# safebox_professional.net
KiCad netlist of a schematic drawn in EAGLE
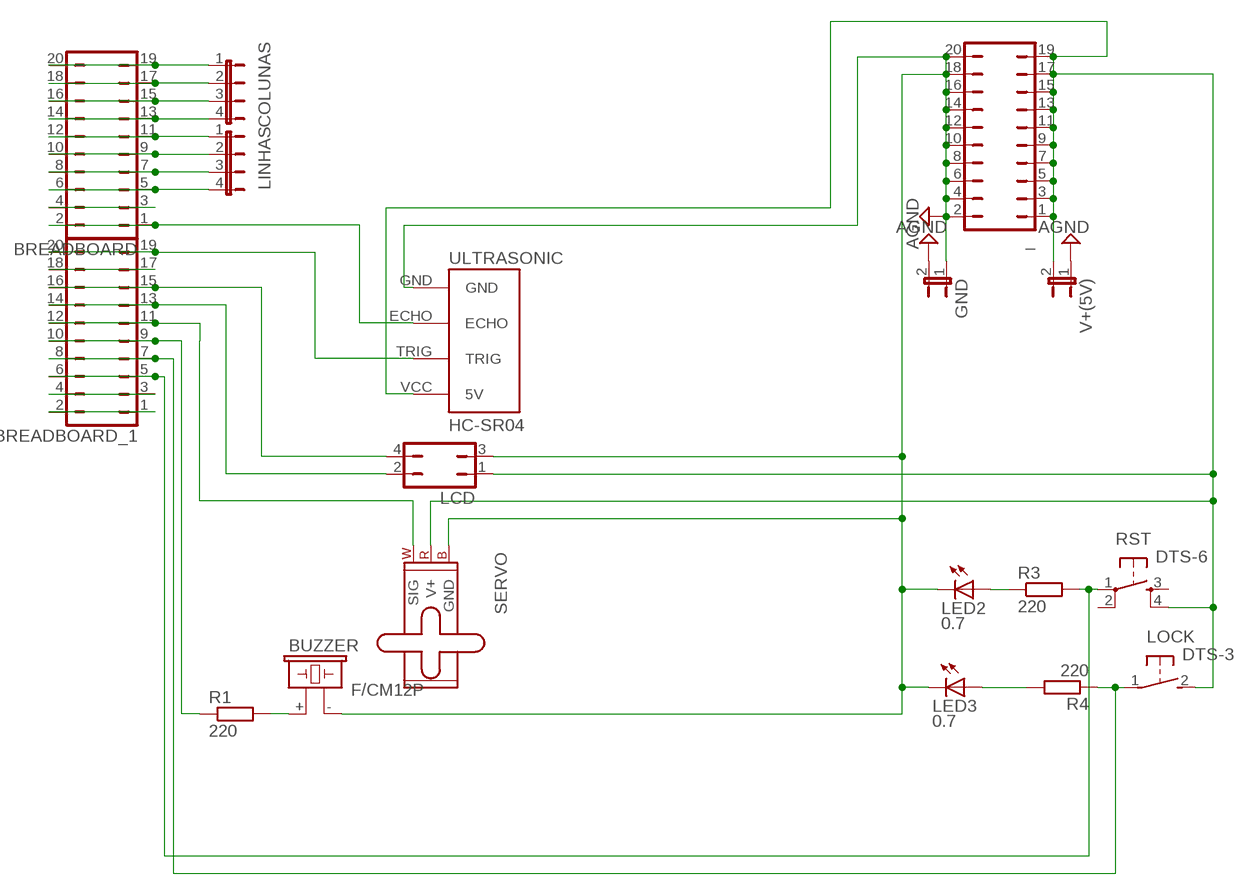
[diagram p0: schematic, sheet 1]

(export (version "E")
  (design (tool "Eeschema 10.0.6"))
  (components
    (comp (ref "BREADBOARD")
      (value "JP10Q")
      (footprint "eagle-import:JP10Q")
      (libsource (lib "eagle-import") (part "JP10Q"))
    )
    (comp (ref "BREADBOARD_1")
      (value "JP10Q")
      (footprint "eagle-import:JP10Q")
      (libsource (lib "eagle-import") (part "JP10Q"))
    )
    (comp (ref "BUZZER")
      (value "F/CM12P")
      (footprint "eagle-import:F_CM12P")
      (libsource (lib "eagle-import") (part "F/CM12P"))
    )
    (comp (ref "COLUNAS")
      (value "JP4E")
      (footprint "eagle-import:JP4")
      (libsource (lib "eagle-import") (part "JP4E"))
    )
    (comp (ref "GND")
      (value "JP1E")
      (footprint "eagle-import:JP1")
      (libsource (lib "eagle-import") (part "JP1E"))
    )
    (comp (ref "LCD")
      (value "JP2Q")
      (footprint "eagle-import:JP2Q")
      (libsource (lib "eagle-import") (part "JP2Q"))
    )
    (comp (ref "LED2")
      (value "0.7")
      (footprint "eagle-import:LED5MM")
      (libsource (lib "eagle-import") (part "LED5MM"))
    )
    (comp (ref "LED3")
      (value "0.7")
      (footprint "eagle-import:LED5MM")
      (libsource (lib "eagle-import") (part "LED5MM"))
    )
    (comp (ref "LINHAS")
      (value "JP4E")
      (footprint "eagle-import:JP4")
      (libsource (lib "eagle-import") (part "JP4E"))
    )
    (comp (ref "LOCK")
      (value "DTS-3")
      (footprint "eagle-import:DTS-3")
      (libsource (lib "eagle-import") (part "DTS-3"))
    )
    (comp (ref "M2")
      (value "SERVO")
      (footprint "eagle-import:1X03")
      (libsource (lib "eagle-import") (part "SERVO"))
    )
    (comp (ref "R1")
      (value "220")
      (footprint "eagle-import:0207_12")
      (libsource (lib "eagle-import") (part "R-EU_0207/12"))
    )
    (comp (ref "R3")
      (value "220")
      (footprint "eagle-import:0207_12")
      (libsource (lib "eagle-import") (part "R-EU_0207/12"))
    )
    (comp (ref "R4")
      (value "220")
      (footprint "eagle-import:0207_12")
      (libsource (lib "eagle-import") (part "R-EU_0207/12"))
    )
    (comp (ref "RST")
      (value "DTS-6")
      (footprint "eagle-import:DTS-6")
      (libsource (lib "eagle-import") (part "DTS-6"))
    )
    (comp (ref "ULTRASONIC")
      (value "HC-SR04")
      (footprint "eagle-import:HC-SR04_FOOTPRINT")
      (libsource (lib "eagle-import") (part "HC-SR04"))
    )
    (comp (ref "V+(5V)")
      (value "JP1E")
      (footprint "eagle-import:JP1")
      (libsource (lib "eagle-import") (part "JP1E"))
    )
    (comp (ref "_")
      (value "JP10Q")
      (footprint "eagle-import:JP10Q")
      (libsource (lib "eagle-import") (part "JP10Q"))
    )
  )
  (nets
    (net (code "1") (name "AGND") (class "Default")
      (node (ref "BUZZER") (pin "-") (pinfunction "2_-") (pintype "passive"))
      (node (ref "GND") (pin "1") (pinfunction "1_1") (pintype "passive"))
      (node (ref "GND") (pin "2") (pinfunction "2_2") (pintype "passive"))
      (node (ref "LCD") (pin "3") (pinfunction "3_3") (pintype "passive"))
      (node (ref "LED2") (pin "K") (pinfunction "C_K") (pintype "passive"))
      (node (ref "LED3") (pin "K") (pinfunction "C_K") (pintype "passive"))
      (node (ref "M2") (pin "3") (pinfunction "GND_3") (pintype "bidirectional"))
      (node (ref "ULTRASONIC") (pin "GND") (pinfunction "GND_GND") (pintype "bidirectional"))
      (node (ref "V+(5V)") (pin "1") (pinfunction "1_1") (pintype "passive"))
      (node (ref "_") (pin "10") (pinfunction "10_10") (pintype "passive"))
      (node (ref "_") (pin "12") (pinfunction "12_12") (pintype "passive"))
      (node (ref "_") (pin "14") (pinfunction "14_14") (pintype "passive"))
      (node (ref "_") (pin "16") (pinfunction "16_16") (pintype "passive"))
      (node (ref "_") (pin "18") (pinfunction "18_18") (pintype "passive"))
      (node (ref "_") (pin "2") (pinfunction "2_2") (pintype "passive"))
      (node (ref "_") (pin "20") (pinfunction "20_20") (pintype "passive"))
      (node (ref "_") (pin "4") (pinfunction "4_4") (pintype "passive"))
      (node (ref "_") (pin "6") (pinfunction "6_6") (pintype "passive"))
      (node (ref "_") (pin "8") (pinfunction "8_8") (pintype "passive"))
    )
    (net (code "2") (name "Net-(BREADBOARD-Pad1)") (class "Default")
      (node (ref "BREADBOARD") (pin "1") (pinfunction "1_1") (pintype "passive"))
      (node (ref "BREADBOARD") (pin "2") (pinfunction "2_2") (pintype "passive"))
      (node (ref "ULTRASONIC") (pin "ECHO") (pinfunction "ECHO_ECHO") (pintype "bidirectional"))
    )
    (net (code "3") (name "Net-(BREADBOARD-Pad3)") (class "Default")
      (node (ref "BREADBOARD") (pin "3") (pinfunction "3_3") (pintype "passive"))
      (node (ref "BREADBOARD") (pin "4") (pinfunction "4_4") (pintype "passive"))
    )
    (net (code "4") (name "Net-(BREADBOARD-Pad5)") (class "Default")
      (node (ref "BREADBOARD") (pin "5") (pinfunction "5_5") (pintype "passive"))
      (node (ref "BREADBOARD") (pin "6") (pinfunction "6_6") (pintype "passive"))
      (node (ref "LINHAS") (pin "4") (pinfunction "4_4") (pintype "passive"))
    )
    (net (code "5") (name "Net-(BREADBOARD-Pad7)") (class "Default")
      (node (ref "BREADBOARD") (pin "7") (pinfunction "7_7") (pintype "passive"))
      (node (ref "BREADBOARD") (pin "8") (pinfunction "8_8") (pintype "passive"))
      (node (ref "LINHAS") (pin "3") (pinfunction "3_3") (pintype "passive"))
    )
    (net (code "6") (name "Net-(BREADBOARD-Pad10)") (class "Default")
      (node (ref "BREADBOARD") (pin "10") (pinfunction "10_10") (pintype "passive"))
      (node (ref "BREADBOARD") (pin "9") (pinfunction "9_9") (pintype "passive"))
      (node (ref "LINHAS") (pin "2") (pinfunction "2_2") (pintype "passive"))
    )
    (net (code "7") (name "Net-(BREADBOARD-Pad11)") (class "Default")
      (node (ref "BREADBOARD") (pin "11") (pinfunction "11_11") (pintype "passive"))
      (node (ref "BREADBOARD") (pin "12") (pinfunction "12_12") (pintype "passive"))
      (node (ref "LINHAS") (pin "1") (pinfunction "1_1") (pintype "passive"))
    )
    (net (code "8") (name "Net-(BREADBOARD-Pad13)") (class "Default")
      (node (ref "BREADBOARD") (pin "13") (pinfunction "13_13") (pintype "passive"))
      (node (ref "BREADBOARD") (pin "14") (pinfunction "14_14") (pintype "passive"))
      (node (ref "COLUNAS") (pin "4") (pinfunction "4_4") (pintype "passive"))
    )
    (net (code "9") (name "Net-(BREADBOARD-Pad15)") (class "Default")
      (node (ref "BREADBOARD") (pin "15") (pinfunction "15_15") (pintype "passive"))
      (node (ref "BREADBOARD") (pin "16") (pinfunction "16_16") (pintype "passive"))
      (node (ref "COLUNAS") (pin "3") (pinfunction "3_3") (pintype "passive"))
    )
    (net (code "10") (name "Net-(BREADBOARD-Pad17)") (class "Default")
      (node (ref "BREADBOARD") (pin "17") (pinfunction "17_17") (pintype "passive"))
      (node (ref "BREADBOARD") (pin "18") (pinfunction "18_18") (pintype "passive"))
      (node (ref "COLUNAS") (pin "2") (pinfunction "2_2") (pintype "passive"))
    )
    (net (code "11") (name "Net-(BREADBOARD-Pad19)") (class "Default")
      (node (ref "BREADBOARD") (pin "19") (pinfunction "19_19") (pintype "passive"))
      (node (ref "BREADBOARD") (pin "20") (pinfunction "20_20") (pintype "passive"))
      (node (ref "COLUNAS") (pin "1") (pinfunction "1_1") (pintype "passive"))
    )
    (net (code "12") (name "Net-(BREADBOARD_1-Pad1)") (class "Default")
      (node (ref "BREADBOARD_1") (pin "1") (pinfunction "1_1") (pintype "passive"))
      (node (ref "BREADBOARD_1") (pin "2") (pinfunction "2_2") (pintype "passive"))
    )
    (net (code "13") (name "Net-(BREADBOARD_1-Pad3)") (class "Default")
      (node (ref "BREADBOARD_1") (pin "3") (pinfunction "3_3") (pintype "passive"))
      (node (ref "BREADBOARD_1") (pin "4") (pinfunction "4_4") (pintype "passive"))
    )
    (net (code "14") (name "Net-(BREADBOARD_1-Pad5)") (class "Default")
      (node (ref "BREADBOARD_1") (pin "5") (pinfunction "5_5") (pintype "passive"))
      (node (ref "BREADBOARD_1") (pin "6") (pinfunction "6_6") (pintype "passive"))
      (node (ref "R3") (pin "2") (pinfunction "2_2") (pintype "passive"))
      (node (ref "RST") (pin "1") (pinfunction "1_1") (pintype "passive"))
    )
    (net (code "15") (name "Net-(BREADBOARD_1-Pad7)") (class "Default")
      (node (ref "BREADBOARD_1") (pin "7") (pinfunction "7_7") (pintype "passive"))
      (node (ref "BREADBOARD_1") (pin "8") (pinfunction "8_8") (pintype "passive"))
      (node (ref "LOCK") (pin "1") (pinfunction "1_1") (pintype "passive"))
      (node (ref "R4") (pin "1") (pinfunction "1_1") (pintype "passive"))
    )
    (net (code "16") (name "Net-(BREADBOARD_1-Pad10)") (class "Default")
      (node (ref "BREADBOARD_1") (pin "10") (pinfunction "10_10") (pintype "passive"))
      (node (ref "BREADBOARD_1") (pin "9") (pinfunction "9_9") (pintype "passive"))
      (node (ref "R1") (pin "1") (pinfunction "1_1") (pintype "passive"))
    )
    (net (code "17") (name "Net-(BREADBOARD_1-Pad13)") (class "Default")
      (node (ref "BREADBOARD_1") (pin "13") (pinfunction "13_13") (pintype "passive"))
      (node (ref "BREADBOARD_1") (pin "14") (pinfunction "14_14") (pintype "passive"))
      (node (ref "LCD") (pin "2") (pinfunction "2_2") (pintype "passive"))
    )
    (net (code "18") (name "Net-(BREADBOARD_1-Pad15)") (class "Default")
      (node (ref "BREADBOARD_1") (pin "15") (pinfunction "15_15") (pintype "passive"))
      (node (ref "BREADBOARD_1") (pin "16") (pinfunction "16_16") (pintype "passive"))
      (node (ref "LCD") (pin "4") (pinfunction "4_4") (pintype "passive"))
    )
    (net (code "19") (name "Net-(BREADBOARD_1-Pad17)") (class "Default")
      (node (ref "BREADBOARD_1") (pin "17") (pinfunction "17_17") (pintype "passive"))
      (node (ref "BREADBOARD_1") (pin "18") (pinfunction "18_18") (pintype "passive"))
    )
    (net (code "20") (name "Net-(BREADBOARD_1-Pad19)") (class "Default")
      (node (ref "BREADBOARD_1") (pin "19") (pinfunction "19_19") (pintype "passive"))
      (node (ref "BREADBOARD_1") (pin "20") (pinfunction "20_20") (pintype "passive"))
      (node (ref "ULTRASONIC") (pin "TRIG") (pinfunction "TRIG_TRIG") (pintype "bidirectional"))
    )
    (net (code "21") (name "Net-(BUZZER-1)") (class "Default")
      (node (ref "BUZZER") (pin "+") (pinfunction "1_+") (pintype "passive"))
      (node (ref "R1") (pin "2") (pinfunction "2_2") (pintype "passive"))
    )
    (net (code "22") (name "Net-(LED2-PadA)") (class "Default")
      (node (ref "LED2") (pin "A") (pinfunction "A_A") (pintype "passive"))
      (node (ref "R3") (pin "1") (pinfunction "1_1") (pintype "passive"))
    )
    (net (code "23") (name "Net-(LED3-PadA)") (class "Default")
      (node (ref "LED3") (pin "A") (pinfunction "A_A") (pintype "passive"))
      (node (ref "R4") (pin "2") (pinfunction "2_2") (pintype "passive"))
    )
    (net (code "24") (name "Net-(M2-SIG)") (class "Default")
      (node (ref "BREADBOARD_1") (pin "11") (pinfunction "11_11") (pintype "passive"))
      (node (ref "BREADBOARD_1") (pin "12") (pinfunction "12_12") (pintype "passive"))
      (node (ref "M2") (pin "1") (pinfunction "SIG_1") (pintype "bidirectional"))
    )
    (net (code "25") (name "Net-(M2-V+)") (class "Default")
      (node (ref "LCD") (pin "1") (pinfunction "1_1") (pintype "passive"))
      (node (ref "LOCK") (pin "2") (pinfunction "2_2") (pintype "passive"))
      (node (ref "M2") (pin "2") (pinfunction "V+_2") (pintype "bidirectional"))
      (node (ref "RST") (pin "4") (pinfunction "4_4") (pintype "passive"))
      (node (ref "ULTRASONIC") (pin "VCC") (pinfunction "5V_VCC") (pintype "bidirectional"))
      (node (ref "V+(5V)") (pin "2") (pinfunction "2_2") (pintype "passive"))
      (node (ref "_") (pin "1") (pinfunction "1_1") (pintype "passive"))
      (node (ref "_") (pin "11") (pinfunction "11_11") (pintype "passive"))
      (node (ref "_") (pin "13") (pinfunction "13_13") (pintype "passive"))
      (node (ref "_") (pin "15") (pinfunction "15_15") (pintype "passive"))
      (node (ref "_") (pin "17") (pinfunction "17_17") (pintype "passive"))
      (node (ref "_") (pin "19") (pinfunction "19_19") (pintype "passive"))
      (node (ref "_") (pin "3") (pinfunction "3_3") (pintype "passive"))
      (node (ref "_") (pin "5") (pinfunction "5_5") (pintype "passive"))
      (node (ref "_") (pin "7") (pinfunction "7_7") (pintype "passive"))
      (node (ref "_") (pin "9") (pinfunction "9_9") (pintype "passive"))
    )
    (net (code "26") (name "unconnected-(RST-Pad2)") (class "Default")
      (node (ref "RST") (pin "2") (pinfunction "2_2") (pintype "passive"))
    )
    (net (code "27") (name "unconnected-(RST-Pad3)") (class "Default")
      (node (ref "RST") (pin "3") (pinfunction "3_3") (pintype "passive"))
    )
  )
)
